# MCU.net
KiCad netlist of a schematic drawn in Altium Designer
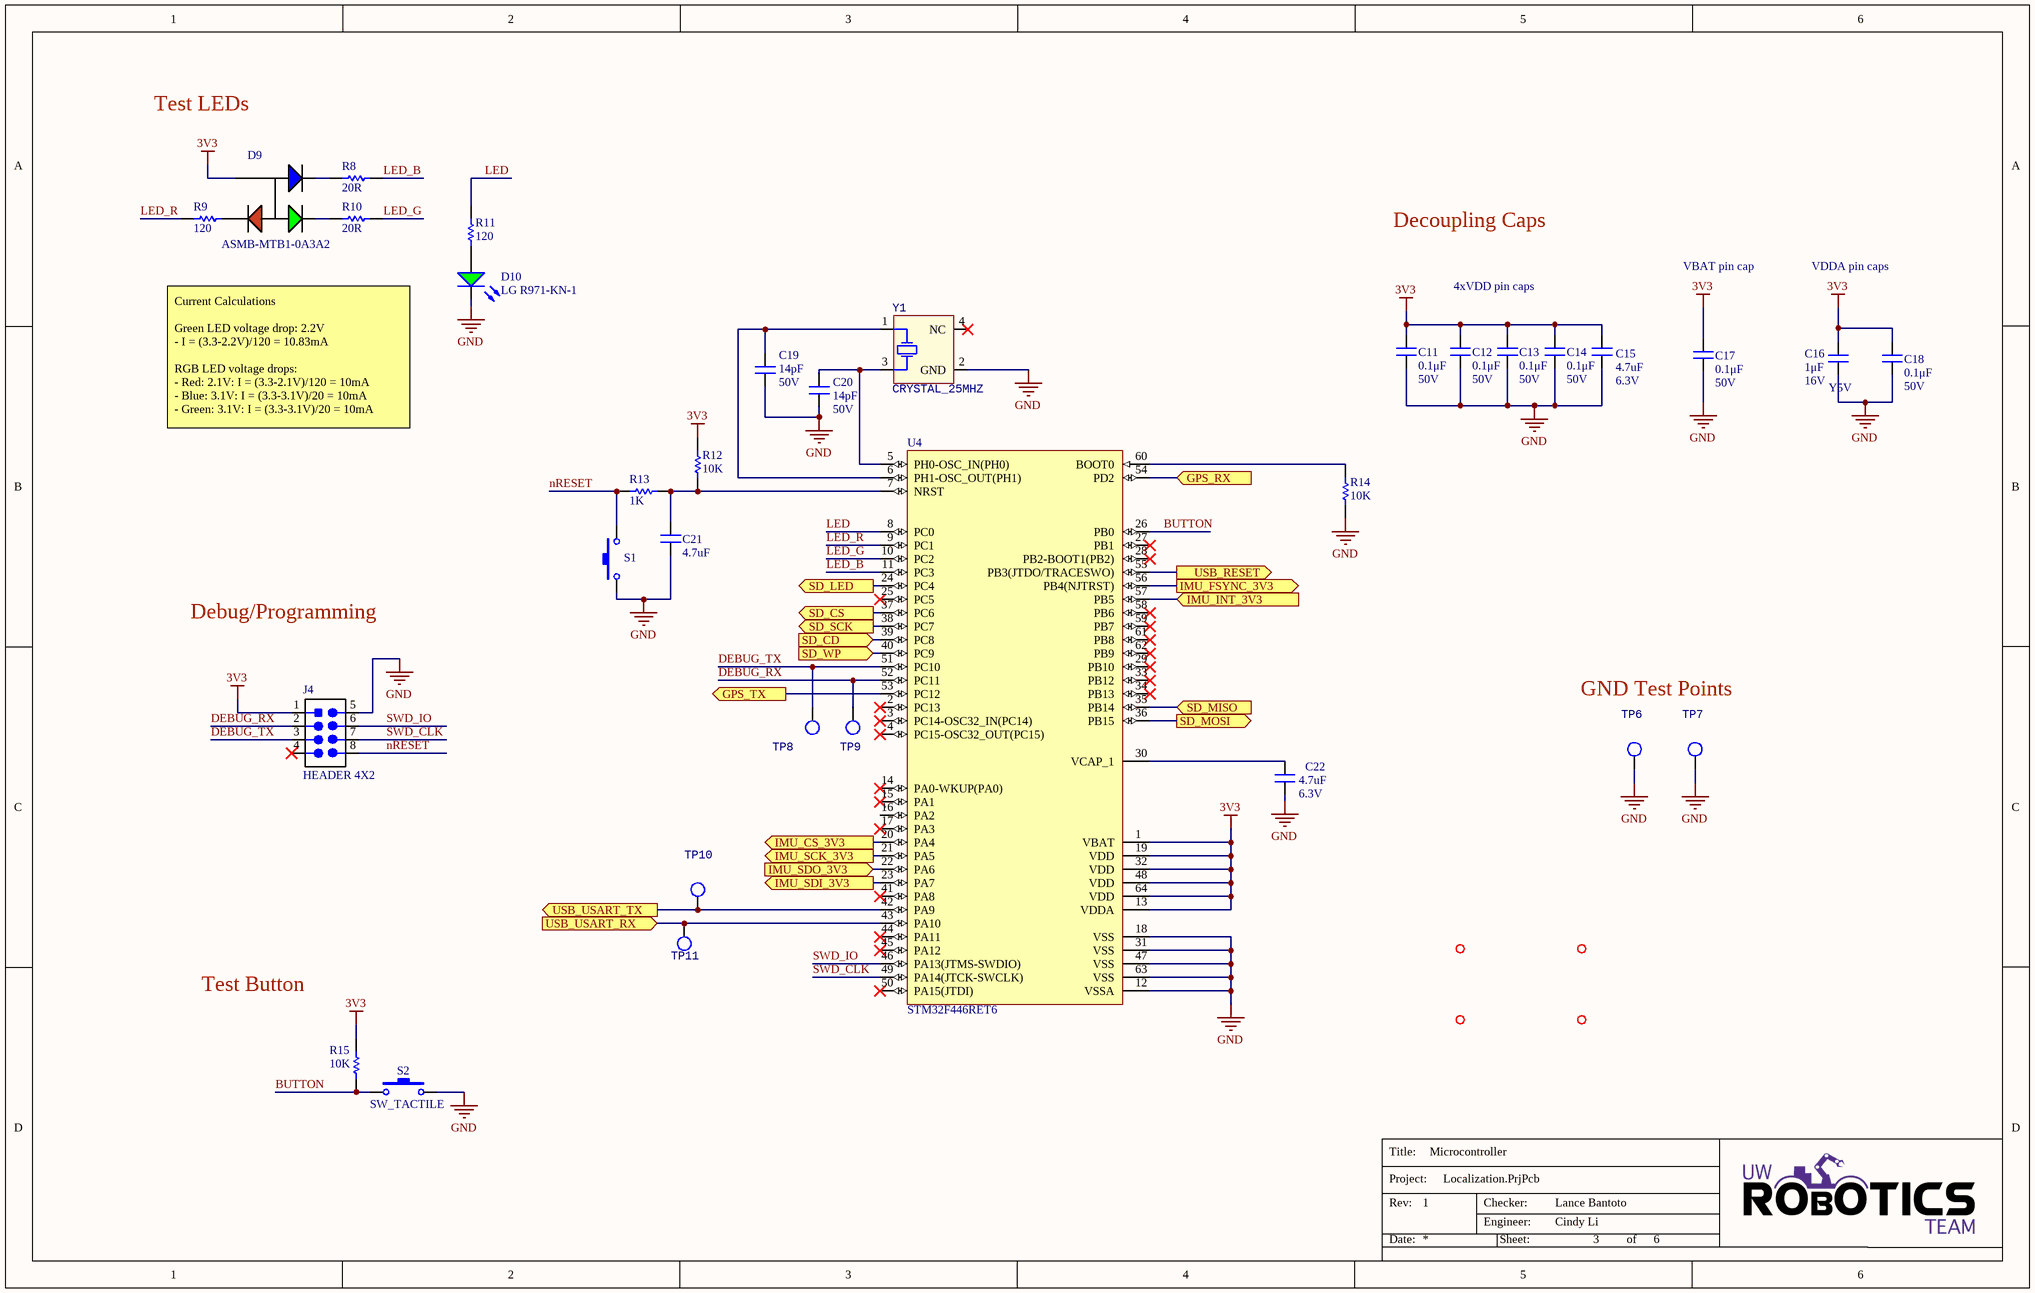
[diagram p0: MCU.SchDoc]

(export (version "E")
  (design (tool "Eeschema 10.0.6"))
  (components
    (comp (ref "C11")
      (value "0.1μF")
      (footprint "CAP2012")
      (description "CAP CER 0.1UF 50V X7R 0805")
      (fields
        (field (name "TOLERANCE") "10%")
        (field (name "VOLTAGE RATING") "50V")
        (field (name "Comment") "CAP_0.1uF_50V_0805")
      )
      (libsource (lib "UWRT_Schematic_Library_2020") (part "CAP_0.1uF_50V_0805"))
    )
    (comp (ref "C12")
      (value "0.1μF")
      (footprint "CAP2012")
      (description "CAP CER 0.1UF 50V X7R 0805")
      (fields
        (field (name "TOLERANCE") "10%")
        (field (name "VOLTAGE RATING") "50V")
        (field (name "Comment") "CAP_0.1uF_50V_0805")
      )
      (libsource (lib "UWRT_Schematic_Library_2020") (part "CAP_0.1uF_50V_0805"))
    )
    (comp (ref "C13")
      (value "0.1μF")
      (footprint "CAP2012")
      (description "CAP CER 0.1UF 50V X7R 0805")
      (fields
        (field (name "TOLERANCE") "10%")
        (field (name "VOLTAGE RATING") "50V")
        (field (name "Comment") "CAP_0.1uF_50V_0805")
      )
      (libsource (lib "UWRT_Schematic_Library_2020") (part "CAP_0.1uF_50V_0805"))
    )
    (comp (ref "C14")
      (value "0.1μF")
      (footprint "CAP2012")
      (description "CAP CER 0.1UF 50V X7R 0805")
      (fields
        (field (name "TOLERANCE") "10%")
        (field (name "VOLTAGE RATING") "50V")
        (field (name "Comment") "CAP_0.1uF_50V_0805")
      )
      (libsource (lib "UWRT_Schematic_Library_2020") (part "CAP_0.1uF_50V_0805"))
    )
    (comp (ref "C15")
      (value "4.7uF")
      (footprint "CAPC0603(1608)55_N")
      (description "CAP CER 4.7UF 6.3V X5R 0603")
      (fields (field (name "VOLTAGE RATING") "6.3V") (field (name "Comment") "CAP_4.7uF_0603"))
      (libsource (lib "UWRT_Schematic_Library_2020") (part "CAP_4.7uF_0603"))
    )
    (comp (ref "C16")
      (value "1μF")
      (footprint "CAP0603")
      (description "CAP CER 1UF 16V Y5V 0603")
      (fields
        (field (name "VOLTAGE RATING") "16V")
        (field (name "MANUFACTURER PART NUMBER") "CC0603ZRY5V7BB105")
        (field (name "DIELECTRIC") "Y5V")
        (field (name "Comment") "CAP_1uF_16V_0603")
      )
      (libsource (lib "UWRT_Schematic_Library_2020") (part "CAP_1uF_16V_0603"))
    )
    (comp (ref "C17")
      (value "0.1μF")
      (footprint "CAP2012")
      (description "CAP CER 0.1UF 50V X7R 0805")
      (fields
        (field (name "TOLERANCE") "10%")
        (field (name "VOLTAGE RATING") "50V")
        (field (name "Comment") "CAP_0.1uF_50V_0805")
      )
      (libsource (lib "UWRT_Schematic_Library_2020") (part "CAP_0.1uF_50V_0805"))
    )
    (comp (ref "C18")
      (value "0.1μF")
      (footprint "CAP2012")
      (description "CAP CER 0.1UF 50V X7R 0805")
      (fields
        (field (name "TOLERANCE") "10%")
        (field (name "VOLTAGE RATING") "50V")
        (field (name "Comment") "CAP_0.1uF_50V_0805")
      )
      (libsource (lib "UWRT_Schematic_Library_2020") (part "CAP_0.1uF_50V_0805"))
    )
    (comp (ref "C19")
      (value "14pF")
      (footprint "CAPC0603(1608)55_N")
      (description "Cap Ceramic 14pF 50V C0G 5% SMD 0603 125C Cardboard T/R")
      (fields
        (field (name "TOLERANCE") "5%")
        (field (name "VOLTAGE RATING (DC)") "50V")
        (field (name "Comment") "CL10C140JB8NNNC")
      )
      (libsource (lib "UWRT_Schematic_Library_2020") (part "CL10C140JB8NNNC"))
    )
    (comp (ref "C20")
      (value "14pF")
      (footprint "CAPC0603(1608)55_N")
      (description "Cap Ceramic 14pF 50V C0G 5% SMD 0603 125C Cardboard T/R")
      (fields
        (field (name "TOLERANCE") "5%")
        (field (name "VOLTAGE RATING (DC)") "50V")
        (field (name "Comment") "CL10C140JB8NNNC")
      )
      (libsource (lib "UWRT_Schematic_Library_2020") (part "CL10C140JB8NNNC"))
    )
    (comp (ref "C21")
      (value "4.7uF")
      (footprint "CAPC0603(1608)55_N")
      (description "CAP CER 4.7UF 6.3V X5R 0603")
      (fields (field (name "Comment") "CAP_4.7uF_0603"))
      (libsource (lib "UWRT_Schematic_Library_2020") (part "CAP_4.7uF_0603"))
    )
    (comp (ref "C22")
      (value "4.7uF")
      (footprint "CAPC0603(1608)55_N")
      (description "CAP CER 4.7UF 6.3V X5R 0603")
      (fields (field (name "VOLTAGE RATING") "6.3V") (field (name "Comment") "CAP_4.7uF_0603"))
      (libsource (lib "UWRT_Schematic_Library_2020") (part "CAP_4.7uF_0603"))
    )
    (comp (ref "D9")
      (value "LED_RGB")
      (footprint "LED_RGB")
      (description "LED RGB DIFFUSED 4PLCC SMD")
      (fields (field (name "MANUFACTURER PART NUMBER 1") "ASMB-MTB1-0A3A2"))
      (libsource (lib "UWRT_Schematic_Library_2020") (part "LED_RGB"))
    )
    (comp (ref "D10")
      (value "LG R971-KN-1")
      (footprint "LED_0805_GREEN")
      (description "LED GREEN DIFFUSED 0805 SMD")
      (libsource (lib "UWRT_Schematic_Library_2020") (part "DIO_LED_G"))
    )
    (comp (ref "J4")
      (value "HEADER 4X2")
      (footprint "HEADER_2X4")
      (description "CONN HEADER VERT 8POS 2.54MM")
      (libsource (lib "UWRT_Schematic_Library_2020") (part "HEADER 4X2"))
    )
    (comp (ref "MH1")
      (value "MOUNTING_HOLES")
      (footprint "MOUNTING_HOLE")
      (description "6cm x 6cm")
      (libsource (lib "UWRT_Schematic_Library_2020") (part "MOUNTING_HOLES"))
    )
    (comp (ref "MH2")
      (value "MOUNTING_HOLES")
      (footprint "MOUNTING_HOLE")
      (description "6cm x 6cm")
      (libsource (lib "UWRT_Schematic_Library_2020") (part "MOUNTING_HOLES"))
    )
    (comp (ref "MH3")
      (value "MOUNTING_HOLES")
      (footprint "MOUNTING_HOLE")
      (description "6cm x 6cm")
      (libsource (lib "UWRT_Schematic_Library_2020") (part "MOUNTING_HOLES"))
    )
    (comp (ref "MH4")
      (value "MOUNTING_HOLES")
      (footprint "MOUNTING_HOLE")
      (description "6cm x 6cm")
      (libsource (lib "UWRT_Schematic_Library_2020") (part "MOUNTING_HOLES"))
    )
    (comp (ref "R8")
      (value "20R")
      (footprint "RESC0603(1608)_N")
      (description "RES SMD 20 OHM 5% 1/10W 0603")
      (fields (field (name "TOLERANCE") "5%") (field (name "Comment") "RES_20R_0603"))
      (libsource (lib "UWRT_Schematic_Library_2020") (part "RES_20R_0603"))
    )
    (comp (ref "R9")
      (value "120")
      (footprint "RESC0603(1608)_N")
      (description "RES SMD 120 OHM 5% 1/10W 0603")
      (fields (field (name "TOLERANCE") "5%") (field (name "Comment") "RES_120R_0603"))
      (libsource (lib "UWRT_Schematic_Library_2020") (part "RES_120R_0603"))
    )
    (comp (ref "R10")
      (value "20R")
      (footprint "RESC0603(1608)_N")
      (description "RES SMD 20 OHM 5% 1/10W 0603")
      (fields (field (name "TOLERANCE") "5%") (field (name "Comment") "RES_20R_0603"))
      (libsource (lib "UWRT_Schematic_Library_2020") (part "RES_20R_0603"))
    )
    (comp (ref "R11")
      (value "120")
      (footprint "RESC0603(1608)_N")
      (description "RES SMD 120 OHM 5% 1/10W 0603")
      (fields (field (name "TOLERANCE") "5%") (field (name "Comment") "RES_120R_0603"))
      (libsource (lib "UWRT_Schematic_Library_2020") (part "RES_120R_0603"))
    )
    (comp (ref "R12")
      (value "10K")
      (footprint "RESC0603(1608)_N")
      (description "RES SMD 10K OHM 5% 1/10W 0603")
      (fields (field (name "TOLERANCE") "5%") (field (name "Comment") "RES_10K_0603"))
      (libsource (lib "UWRT_Schematic_Library_2020") (part "RES_10K_0603"))
    )
    (comp (ref "R13")
      (value "1K")
      (footprint "RESC0603(1608)_N")
      (description "RES SMD 1K OHM 5% 1/10W 0603")
      (fields (field (name "TOLERANCE") "5%") (field (name "Comment") "RES_1K_0603"))
      (libsource (lib "UWRT_Schematic_Library_2020") (part "RES_1K_0603"))
    )
    (comp (ref "R14")
      (value "10K")
      (footprint "RESC0603(1608)_N")
      (description "RES SMD 10K OHM 5% 1/10W 0603")
      (fields (field (name "TOLERANCE") "5%") (field (name "Comment") "RES_10K_0603"))
      (libsource (lib "UWRT_Schematic_Library_2020") (part "RES_10K_0603"))
    )
    (comp (ref "R15")
      (value "10K")
      (footprint "RESC0603(1608)_N")
      (description "RES SMD 10K OHM 5% 1/10W 0603")
      (fields (field (name "TOLERANCE") "5%") (field (name "Comment") "RES_10K_0603"))
      (libsource (lib "UWRT_Schematic_Library_2020") (part "RES_10K_0603"))
    )
    (comp (ref "S1")
      (value "SW_TACTILE")
      (footprint "B3U-1000P")
      (description "Tactile Switch (Grey)")
      (libsource (lib "UWRT_Schematic_Library_2020") (part "SW_TACTILE"))
    )
    (comp (ref "S2")
      (value "SW_TACTILE")
      (footprint "B3U-1000P")
      (description "Tactile Switch (Grey)")
      (libsource (lib "UWRT_Schematic_Library_2020") (part "SW_TACTILE"))
    )
    (comp (ref "TP6")
      (value "TESTPOINT_LOOP")
      (footprint "TESTPOINT_LOOP")
      (description "PC TEST POINT MINIATURE WHITE")
      (libsource (lib "UWRT_Schematic_Library_2020") (part "TESTPOINT_LOOP"))
    )
    (comp (ref "TP7")
      (value "TESTPOINT_LOOP")
      (footprint "TESTPOINT_LOOP")
      (description "PC TEST POINT MINIATURE WHITE")
      (libsource (lib "UWRT_Schematic_Library_2020") (part "TESTPOINT_LOOP"))
    )
    (comp (ref "TP8")
      (value "TESTPOINT_LOOP")
      (footprint "TESTPOINT_LOOP")
      (description "PC TEST POINT MINIATURE WHITE")
      (libsource (lib "UWRT_Schematic_Library_2020") (part "TESTPOINT_LOOP"))
    )
    (comp (ref "TP9")
      (value "TESTPOINT_LOOP")
      (footprint "TESTPOINT_LOOP")
      (description "PC TEST POINT MINIATURE WHITE")
      (libsource (lib "UWRT_Schematic_Library_2020") (part "TESTPOINT_LOOP"))
    )
    (comp (ref "TP10")
      (value "TESTPOINT_LOOP")
      (footprint "TESTPOINT_LOOP")
      (description "PC TEST POINT MINIATURE WHITE")
      (libsource (lib "UWRT_Schematic_Library_2020") (part "TESTPOINT_LOOP"))
    )
    (comp (ref "TP11")
      (value "TESTPOINT_LOOP")
      (footprint "TESTPOINT_LOOP")
      (description "PC TEST POINT MINIATURE WHITE")
      (libsource (lib "UWRT_Schematic_Library_2020") (part "TESTPOINT_LOOP"))
    )
    (comp (ref "U4")
      (value "STM32F446RET6")
      (footprint "STM-LQFP64_L")
      (libsource (lib "UWRT_Schematic_Library_2020") (part "MCU_STM32F446RET6"))
    )
    (comp (ref "Y1")
      (value "CRYSTAL_25MHZ")
      (footprint "SOIC254P1016X440-4N")
      (description "CRYSTAL 25.0000MHZ 12PF SMD")
      (libsource (lib "UWRT_Schematic_Library_2020") (part "CRYSTAL_25MHZ"))
    )
  )
  (nets
    (net (code "1") (name "/BUTTON") (class "Default")
      (node (ref "R15") (pin "2") (pinfunction "2_2") (pintype "passive"))
      (node (ref "S2") (pin "1") (pinfunction "1_1") (pintype "passive"))
      (node (ref "U4") (pin "26") (pinfunction "PB0_26") (pintype "bidirectional"))
    )
    (net (code "2") (name "/DEBUG_RX") (class "Default")
      (node (ref "J4") (pin "2") (pinfunction "2_2") (pintype "passive"))
      (node (ref "TP9") (pin "1") (pintype "passive"))
      (node (ref "U4") (pin "52") (pinfunction "PC11_52") (pintype "bidirectional"))
    )
    (net (code "3") (name "/DEBUG_TX") (class "Default")
      (node (ref "J4") (pin "3") (pinfunction "3_3") (pintype "passive"))
      (node (ref "TP8") (pin "1") (pintype "passive"))
      (node (ref "U4") (pin "51") (pinfunction "PC10_51") (pintype "bidirectional"))
    )
    (net (code "4") (name "/GPS_RX") (class "Default")
      (node (ref "U4") (pin "54") (pinfunction "PD2_54") (pintype "bidirectional"))
    )
    (net (code "5") (name "/GPS_TX") (class "Default")
      (node (ref "U4") (pin "53") (pinfunction "PC12_53") (pintype "bidirectional"))
    )
    (net (code "6") (name "/IMU_CS_3V3") (class "Default")
      (node (ref "U4") (pin "20") (pinfunction "PA4_20") (pintype "bidirectional"))
    )
    (net (code "7") (name "/IMU_FSYNC_3V3") (class "Default")
      (node (ref "U4") (pin "56") (pinfunction "PB4(NJTRST)_56") (pintype "bidirectional"))
    )
    (net (code "8") (name "/IMU_INT_3V3") (class "Default")
      (node (ref "U4") (pin "57") (pinfunction "PB5_57") (pintype "bidirectional"))
    )
    (net (code "9") (name "/IMU_SCK_3V3") (class "Default")
      (node (ref "U4") (pin "21") (pinfunction "PA5_21") (pintype "bidirectional"))
    )
    (net (code "10") (name "/IMU_SDI_3V3") (class "Default")
      (node (ref "U4") (pin "23") (pinfunction "PA7_23") (pintype "bidirectional"))
    )
    (net (code "11") (name "/IMU_SDO_3V3") (class "Default")
      (node (ref "U4") (pin "22") (pinfunction "PA6_22") (pintype "bidirectional"))
    )
    (net (code "12") (name "/LED") (class "Default")
      (node (ref "R11") (pin "1") (pinfunction "1_1") (pintype "passive"))
      (node (ref "U4") (pin "8") (pinfunction "PC0_8") (pintype "bidirectional"))
    )
    (net (code "13") (name "/LED_B") (class "Default")
      (node (ref "R8") (pin "2") (pinfunction "2_2") (pintype "passive"))
      (node (ref "U4") (pin "11") (pinfunction "PC3_11") (pintype "bidirectional"))
    )
    (net (code "14") (name "/LED_G") (class "Default")
      (node (ref "R10") (pin "2") (pinfunction "2_2") (pintype "passive"))
      (node (ref "U4") (pin "10") (pinfunction "PC2_10") (pintype "bidirectional"))
    )
    (net (code "15") (name "/LED_R") (class "Default")
      (node (ref "R9") (pin "1") (pinfunction "1_1") (pintype "passive"))
      (node (ref "U4") (pin "9") (pinfunction "PC1_9") (pintype "bidirectional"))
    )
    (net (code "16") (name "/SD_CD") (class "Default")
      (node (ref "U4") (pin "39") (pinfunction "PC8_39") (pintype "bidirectional"))
    )
    (net (code "17") (name "/SD_CS") (class "Default")
      (node (ref "U4") (pin "37") (pinfunction "PC6_37") (pintype "bidirectional"))
    )
    (net (code "18") (name "/SD_LED") (class "Default")
      (node (ref "U4") (pin "24") (pinfunction "PC4_24") (pintype "bidirectional"))
    )
    (net (code "19") (name "/SD_MISO") (class "Default")
      (node (ref "U4") (pin "35") (pinfunction "PB14_35") (pintype "bidirectional"))
    )
    (net (code "20") (name "/SD_MOSI") (class "Default")
      (node (ref "U4") (pin "36") (pinfunction "PB15_36") (pintype "bidirectional"))
    )
    (net (code "21") (name "/SD_SCK") (class "Default")
      (node (ref "U4") (pin "38") (pinfunction "PC7_38") (pintype "bidirectional"))
    )
    (net (code "22") (name "/SD_WP") (class "Default")
      (node (ref "U4") (pin "40") (pinfunction "PC9_40") (pintype "bidirectional"))
    )
    (net (code "23") (name "/SWD_CLK") (class "Default")
      (node (ref "J4") (pin "7") (pinfunction "3_7") (pintype "passive"))
      (node (ref "U4") (pin "49") (pinfunction "PA14(JTCK-SWCLK)_49") (pintype "bidirectional"))
    )
    (net (code "24") (name "/SWD_IO") (class "Default")
      (node (ref "J4") (pin "6") (pinfunction "2_6") (pintype "passive"))
      (node (ref "U4") (pin "46") (pinfunction "PA13(JTMS-SWDIO)_46") (pintype "bidirectional"))
    )
    (net (code "25") (name "/USB_RESET") (class "Default")
      (node (ref "U4") (pin "55") (pinfunction "PB3(JTDO/TRACESWO)_55") (pintype "bidirectional"))
    )
    (net (code "26") (name "/USB_USART_RX") (class "Default")
      (node (ref "TP11") (pin "1") (pintype "passive"))
      (node (ref "U4") (pin "43") (pinfunction "PA10_43") (pintype "bidirectional"))
    )
    (net (code "27") (name "/USB_USART_TX") (class "Default")
      (node (ref "TP10") (pin "1") (pintype "passive"))
      (node (ref "U4") (pin "42") (pinfunction "PA9_42") (pintype "bidirectional"))
    )
    (net (code "28") (name "/nRESET") (class "Default")
      (node (ref "J4") (pin "8") (pinfunction "4_8") (pintype "passive"))
      (node (ref "R13") (pin "1") (pinfunction "1_1") (pintype "passive"))
      (node (ref "S1") (pin "2") (pinfunction "2_2") (pintype "passive"))
    )
    (net (code "29") (name "3V3") (class "Default")
      (node (ref "C11") (pin "2") (pinfunction "2_2") (pintype "passive"))
      (node (ref "C12") (pin "2") (pinfunction "2_2") (pintype "passive"))
      (node (ref "C13") (pin "2") (pinfunction "2_2") (pintype "passive"))
      (node (ref "C14") (pin "2") (pinfunction "2_2") (pintype "passive"))
      (node (ref "C15") (pin "2") (pinfunction "2_2") (pintype "passive"))
      (node (ref "C16") (pin "2") (pinfunction "2_2") (pintype "passive"))
      (node (ref "C17") (pin "2") (pinfunction "2_2") (pintype "passive"))
      (node (ref "C18") (pin "2") (pinfunction "2_2") (pintype "passive"))
      (node (ref "D9") (pin "4") (pinfunction "COMMON_ANODE_4") (pintype "passive"))
      (node (ref "J4") (pin "1") (pinfunction "VCC_1") (pintype "passive"))
      (node (ref "R12") (pin "2") (pinfunction "2_2") (pintype "passive"))
      (node (ref "R15") (pin "1") (pinfunction "1_1") (pintype "passive"))
      (node (ref "U4") (pin "1") (pinfunction "VBAT_1") (pintype "power_in"))
      (node (ref "U4") (pin "13") (pinfunction "VDDA_13") (pintype "power_in"))
      (node (ref "U4") (pin "19") (pinfunction "VDD_19") (pintype "power_in"))
      (node (ref "U4") (pin "32") (pinfunction "VDD_32") (pintype "power_in"))
      (node (ref "U4") (pin "48") (pinfunction "VDD_48") (pintype "power_in"))
      (node (ref "U4") (pin "64") (pinfunction "VDD_64") (pintype "power_in"))
    )
    (net (code "30") (name "GND") (class "Default")
      (node (ref "C11") (pin "1") (pinfunction "1_1") (pintype "passive"))
      (node (ref "C12") (pin "1") (pinfunction "1_1") (pintype "passive"))
      (node (ref "C13") (pin "1") (pinfunction "1_1") (pintype "passive"))
      (node (ref "C14") (pin "1") (pinfunction "1_1") (pintype "passive"))
      (node (ref "C15") (pin "1") (pinfunction "1_1") (pintype "passive"))
      (node (ref "C16") (pin "1") (pinfunction "1_1") (pintype "passive"))
      (node (ref "C17") (pin "1") (pinfunction "1_1") (pintype "passive"))
      (node (ref "C18") (pin "1") (pinfunction "1_1") (pintype "passive"))
      (node (ref "C19") (pin "1") (pinfunction "1_1") (pintype "passive"))
      (node (ref "C20") (pin "1") (pinfunction "1_1") (pintype "passive"))
      (node (ref "C21") (pin "1") (pinfunction "1_1") (pintype "passive"))
      (node (ref "C22") (pin "1") (pinfunction "1_1") (pintype "passive"))
      (node (ref "D10") (pin "2") (pinfunction "K_2") (pintype "passive"))
      (node (ref "J4") (pin "5") (pinfunction "GND_5") (pintype "passive"))
      (node (ref "R14") (pin "2") (pinfunction "2_2") (pintype "passive"))
      (node (ref "S1") (pin "1") (pinfunction "1_1") (pintype "passive"))
      (node (ref "S2") (pin "2") (pinfunction "2_2") (pintype "passive"))
      (node (ref "TP6") (pin "1") (pintype "passive"))
      (node (ref "TP7") (pin "1") (pintype "passive"))
      (node (ref "U4") (pin "12") (pinfunction "VSSA_12") (pintype "power_in"))
      (node (ref "U4") (pin "18") (pinfunction "VSS_18") (pintype "power_in"))
      (node (ref "U4") (pin "31") (pinfunction "VSS_31") (pintype "power_in"))
      (node (ref "U4") (pin "47") (pinfunction "VSS_47") (pintype "power_in"))
      (node (ref "U4") (pin "63") (pinfunction "VSS_63") (pintype "power_in"))
      (node (ref "Y1") (pin "2") (pinfunction "GND_2") (pintype "power_in"))
    )
    (net (code "31") (name "Net-(D9-CATHODE_(BLUE))") (class "Default")
      (node (ref "D9") (pin "3") (pinfunction "CATHODE_(BLUE)_3") (pintype "passive"))
      (node (ref "R8") (pin "1") (pinfunction "1_1") (pintype "passive"))
    )
    (net (code "32") (name "Net-(D9-CATHODE_(GREEN))") (class "Default")
      (node (ref "D9") (pin "2") (pinfunction "CATHODE_(GREEN)_2") (pintype "passive"))
      (node (ref "R10") (pin "1") (pinfunction "1_1") (pintype "passive"))
    )
    (net (code "33") (name "Net-(D9-CATHODE_(RED))") (class "Default")
      (node (ref "D9") (pin "1") (pinfunction "CATHODE_(RED)_1") (pintype "passive"))
      (node (ref "R9") (pin "2") (pinfunction "2_2") (pintype "passive"))
    )
    (net (code "34") (name "Net-(D10-A)") (class "Default")
      (node (ref "D10") (pin "1") (pinfunction "A_1") (pintype "passive"))
      (node (ref "R11") (pin "2") (pinfunction "2_2") (pintype "passive"))
    )
    (net (code "35") (name "Net-(U4-BOOT0)") (class "Default")
      (node (ref "R14") (pin "1") (pinfunction "1_1") (pintype "passive"))
      (node (ref "U4") (pin "60") (pinfunction "BOOT0_60") (pintype "input"))
    )
    (net (code "36") (name "Net-(U4-NRST)") (class "Default")
      (node (ref "C21") (pin "2") (pinfunction "2_2") (pintype "passive"))
      (node (ref "R12") (pin "1") (pinfunction "1_1") (pintype "passive"))
      (node (ref "R13") (pin "2") (pinfunction "2_2") (pintype "passive"))
      (node (ref "U4") (pin "7") (pinfunction "NRST_7") (pintype "bidirectional"))
    )
    (net (code "37") (name "Net-(U4-PH0-OSC_IN(PH0))") (class "Default")
      (node (ref "C20") (pin "2") (pinfunction "2_2") (pintype "passive"))
      (node (ref "U4") (pin "5") (pinfunction "PH0-OSC_IN(PH0)_5") (pintype "bidirectional"))
      (node (ref "Y1") (pin "3") (pinfunction "HOT_3") (pintype "passive"))
    )
    (net (code "38") (name "Net-(U4-PH1-OSC_OUT(PH1))") (class "Default")
      (node (ref "C19") (pin "2") (pinfunction "2_2") (pintype "passive"))
      (node (ref "U4") (pin "6") (pinfunction "PH1-OSC_OUT(PH1)_6") (pintype "bidirectional"))
      (node (ref "Y1") (pin "1") (pinfunction "HOT_1") (pintype "passive"))
    )
    (net (code "39") (name "Net-(U4-VCAP_1)") (class "Default")
      (node (ref "C22") (pin "2") (pinfunction "2_2") (pintype "passive"))
      (node (ref "U4") (pin "30") (pinfunction "VCAP_1_30") (pintype "passive"))
    )
    (net (code "40") (name "unconnected-(J4-Pad4)") (class "Default")
      (node (ref "J4") (pin "4") (pinfunction "4_4") (pintype "passive+no_connect"))
    )
    (net (code "41") (name "unconnected-(U4-PA0-WKUP(PA0)-Pad14)") (class "Default")
      (node (ref "U4") (pin "14") (pinfunction "PA0-WKUP(PA0)_14") (pintype "bidirectional+no_connect"))
    )
    (net (code "42") (name "unconnected-(U4-PA1-Pad15)") (class "Default")
      (node (ref "U4") (pin "15") (pinfunction "PA1_15") (pintype "bidirectional+no_connect"))
    )
    (net (code "43") (name "unconnected-(U4-PA2-Pad16)") (class "Default")
      (node (ref "U4") (pin "16") (pinfunction "PA2_16") (pintype "bidirectional"))
    )
    (net (code "44") (name "unconnected-(U4-PA3-Pad17)") (class "Default")
      (node (ref "U4") (pin "17") (pinfunction "PA3_17") (pintype "bidirectional+no_connect"))
    )
    (net (code "45") (name "unconnected-(U4-PA8-Pad41)") (class "Default")
      (node (ref "U4") (pin "41") (pinfunction "PA8_41") (pintype "bidirectional+no_connect"))
    )
    (net (code "46") (name "unconnected-(U4-PA11-Pad44)") (class "Default")
      (node (ref "U4") (pin "44") (pinfunction "PA11_44") (pintype "bidirectional+no_connect"))
    )
    (net (code "47") (name "unconnected-(U4-PA12-Pad45)") (class "Default")
      (node (ref "U4") (pin "45") (pinfunction "PA12_45") (pintype "bidirectional+no_connect"))
    )
    (net (code "48") (name "unconnected-(U4-PA15(JTDI)-Pad50)") (class "Default")
      (node (ref "U4") (pin "50") (pinfunction "PA15(JTDI)_50") (pintype "bidirectional+no_connect"))
    )
    (net (code "49") (name "unconnected-(U4-PB1-Pad27)") (class "Default")
      (node (ref "U4") (pin "27") (pinfunction "PB1_27") (pintype "bidirectional+no_connect"))
    )
    (net (code "50") (name "unconnected-(U4-PB2-BOOT1(PB2)-Pad28)") (class "Default")
      (node (ref "U4") (pin "28") (pinfunction "PB2-BOOT1(PB2)_28") (pintype "bidirectional+no_connect"))
    )
    (net (code "51") (name "unconnected-(U4-PB6-Pad58)") (class "Default")
      (node (ref "U4") (pin "58") (pinfunction "PB6_58") (pintype "bidirectional+no_connect"))
    )
    (net (code "52") (name "unconnected-(U4-PB7-Pad59)") (class "Default")
      (node (ref "U4") (pin "59") (pinfunction "PB7_59") (pintype "bidirectional+no_connect"))
    )
    (net (code "53") (name "unconnected-(U4-PB8-Pad61)") (class "Default")
      (node (ref "U4") (pin "61") (pinfunction "PB8_61") (pintype "bidirectional+no_connect"))
    )
    (net (code "54") (name "unconnected-(U4-PB9-Pad62)") (class "Default")
      (node (ref "U4") (pin "62") (pinfunction "PB9_62") (pintype "bidirectional+no_connect"))
    )
    (net (code "55") (name "unconnected-(U4-PB10-Pad29)") (class "Default")
      (node (ref "U4") (pin "29") (pinfunction "PB10_29") (pintype "bidirectional+no_connect"))
    )
    (net (code "56") (name "unconnected-(U4-PB12-Pad33)") (class "Default")
      (node (ref "U4") (pin "33") (pinfunction "PB12_33") (pintype "bidirectional+no_connect"))
    )
    (net (code "57") (name "unconnected-(U4-PB13-Pad34)") (class "Default")
      (node (ref "U4") (pin "34") (pinfunction "PB13_34") (pintype "bidirectional+no_connect"))
    )
    (net (code "58") (name "unconnected-(U4-PC5-Pad25)") (class "Default")
      (node (ref "U4") (pin "25") (pinfunction "PC5_25") (pintype "bidirectional+no_connect"))
    )
    (net (code "59") (name "unconnected-(U4-PC13-Pad2)") (class "Default")
      (node (ref "U4") (pin "2") (pinfunction "PC13_2") (pintype "bidirectional+no_connect"))
    )
    (net (code "60") (name "unconnected-(U4-PC14-OSC32_IN(PC14)-Pad3)") (class "Default")
      (node (ref "U4") (pin "3") (pinfunction "PC14-OSC32_IN(PC14)_3") (pintype "bidirectional+no_connect"))
    )
    (net (code "61") (name "unconnected-(U4-PC15-OSC32_OUT(PC15)-Pad4)") (class "Default")
      (node (ref "U4") (pin "4") (pinfunction "PC15-OSC32_OUT(PC15)_4") (pintype "bidirectional+no_connect"))
    )
    (net (code "62") (name "unconnected-(Y1-NC-Pad4)") (class "Default")
      (node (ref "Y1") (pin "4") (pinfunction "NC_4") (pintype "passive+no_connect"))
    )
  )
)
